# IAQ-core.net
KiCad netlist of a schematic drawn in EAGLE
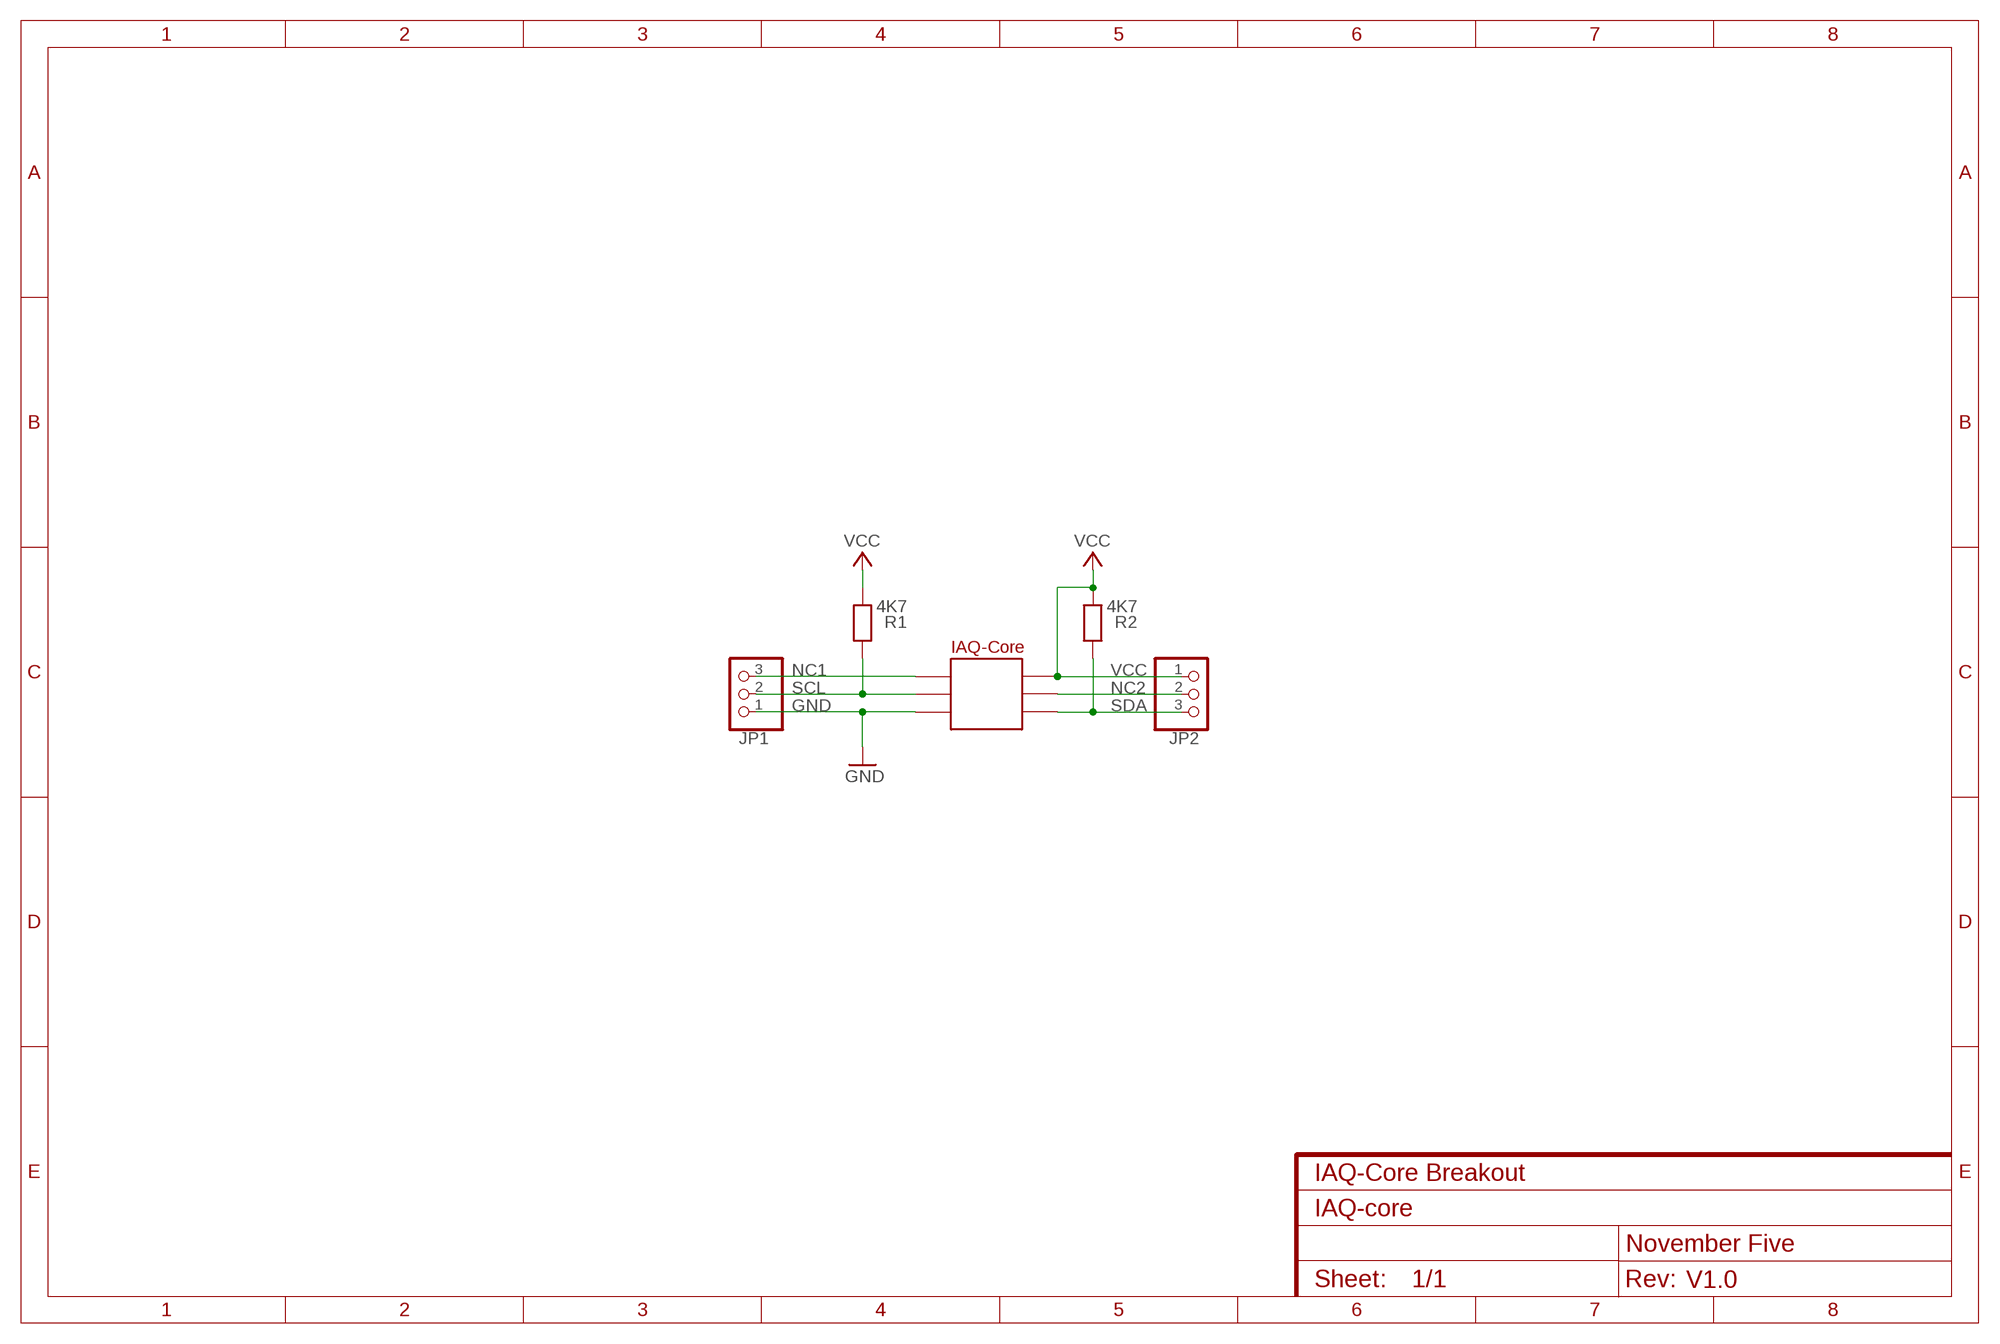
[diagram p0: schematic, sheet 1]

(export (version "E")
  (design (tool "Eeschema 10.0.6"))
  (components
    (comp (ref "IAQ-CORE")
      (value "IAQ-CORE")
      (footprint "eagle-import:IAQ-CORE")
      (libsource (lib "eagle-import") (part "IAQ-CORE"))
    )
    (comp (ref "JP1")
      (value "PINHD-1X3")
      (footprint "eagle-import:1X03")
      (libsource (lib "eagle-import") (part "PINHD-1X3"))
    )
    (comp (ref "JP2")
      (value "PINHD-1X3")
      (footprint "eagle-import:1X03")
      (libsource (lib "eagle-import") (part "PINHD-1X3"))
    )
    (comp (ref "R1")
      (value "4K7")
      (footprint "eagle-import:R0603")
      (libsource (lib "eagle-import") (part "RESISTOR"))
    )
    (comp (ref "R2")
      (value "4K7")
      (footprint "eagle-import:R0603")
      (libsource (lib "eagle-import") (part "RESISTOR"))
    )
  )
  (nets
    (net (code "1") (name "/NC1") (class "Default")
      (node (ref "IAQ-CORE") (pin "NC1") (pinfunction "NC1_NC1") (pintype "bidirectional"))
      (node (ref "JP1") (pin "3") (pinfunction "3_3") (pintype "passive"))
    )
    (net (code "2") (name "/NC2") (class "Default")
      (node (ref "IAQ-CORE") (pin "NC2") (pinfunction "NC2_NC2") (pintype "bidirectional"))
      (node (ref "JP2") (pin "2") (pinfunction "2_2") (pintype "passive"))
    )
    (net (code "3") (name "/SCL") (class "Default")
      (node (ref "IAQ-CORE") (pin "SCL") (pinfunction "SCL_SCL") (pintype "bidirectional"))
      (node (ref "JP1") (pin "2") (pinfunction "2_2") (pintype "passive"))
      (node (ref "R1") (pin "1") (pinfunction "1_1") (pintype "passive"))
    )
    (net (code "4") (name "/SDA") (class "Default")
      (node (ref "IAQ-CORE") (pin "SDA") (pinfunction "SDA_SDA") (pintype "bidirectional"))
      (node (ref "JP2") (pin "3") (pinfunction "3_3") (pintype "passive"))
      (node (ref "R2") (pin "1") (pinfunction "1_1") (pintype "passive"))
    )
    (net (code "5") (name "GND") (class "Default")
      (node (ref "IAQ-CORE") (pin "GND") (pinfunction "GND_GND") (pintype "bidirectional"))
      (node (ref "JP1") (pin "1") (pinfunction "1_1") (pintype "passive"))
    )
    (net (code "6") (name "VCC") (class "Default")
      (node (ref "IAQ-CORE") (pin "VCC") (pinfunction "VCC_VCC") (pintype "bidirectional"))
      (node (ref "JP2") (pin "1") (pinfunction "1_1") (pintype "passive"))
      (node (ref "R1") (pin "2") (pinfunction "2_2") (pintype "passive"))
      (node (ref "R2") (pin "2") (pinfunction "2_2") (pintype "passive"))
    )
  )
)
